# MUX.net
KiCad netlist of a schematic drawn in Altium Designer
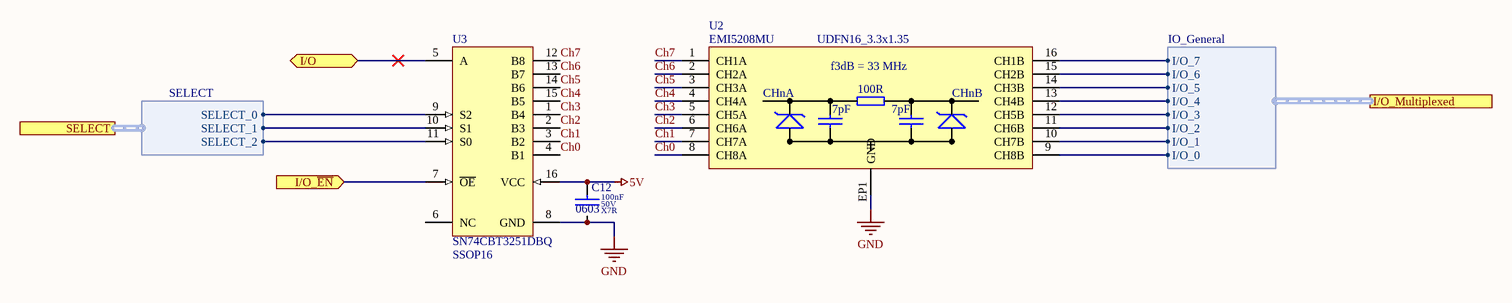
[diagram p0: MUX.SchDoc]

(export (version "E")
  (design (tool "Eeschema 10.0.6"))
  (components
    (comp (ref "C12")
      (value "100nF")
      (footprint "C_0603_1608")
      (description "Capacitor")
      (fields
        (field (name "DIELECTRIC") "X7R")
        (field (name "VOLTAGE") "50V")
        (field (name "SCH_FOOTPRINT") "0603")
        (field (name "PART NUMBER") "C_100nF_50V_X7R_0603_5")
        (field (name "MANUFACTURER") "Samsung")
      )
      (libsource (lib "Library") (part "C"))
    )
    (comp (ref "U2")
      (value "EMI5208MU")
      (footprint "UDFN16_3.3x1.35")
      (description "8 - channel esd-protection + lo-pass filter")
      (fields
        (field (name "SCH_FOOTPRINT") "UDFN16_3.3x1.35")
        (field (name "PART NUMBER") "U_EMI5208MU")
        (field (name "MANUFACTURER") "ON Semiconductor")
      )
      (libsource (lib "Library") (part "U_EMI5208MU"))
    )
    (comp (ref "U3")
      (value "SN74CBT3251DBQ")
      (footprint "SSOP16_4.9x3.9")
      (fields
        (field (name "PART NUMBER") "U_SN74CBT3251DBQ")
        (field (name "SCH_FOOTPRINT") "SSOP16")
        (field (name "MANUFACTURER") "Texas Instruments")
        (field (name "Comment") "1-of-8 FET Multiplexer and Demultiplexer")
      )
      (libsource (lib "Library") (part "U_SN74CBT3251"))
    )
  )
  (nets
    (net (code "3") (name "/Ch0") (class "Default")
      (node (ref "U2") (pin "8") (pinfunction "CH8A_8") (pintype "passive"))
      (node (ref "U3") (pin "4") (pinfunction "B1_4") (pintype "passive"))
    )
    (net (code "4") (name "/Ch1") (class "Default")
      (node (ref "U2") (pin "7") (pinfunction "CH7A_7") (pintype "passive"))
      (node (ref "U3") (pin "3") (pinfunction "B2_3") (pintype "passive"))
    )
    (net (code "5") (name "/Ch2") (class "Default")
      (node (ref "U2") (pin "6") (pinfunction "CH6A_6") (pintype "passive"))
      (node (ref "U3") (pin "2") (pinfunction "B3_2") (pintype "passive"))
    )
    (net (code "6") (name "/Ch3") (class "Default")
      (node (ref "U2") (pin "5") (pinfunction "CH5A_5") (pintype "passive"))
      (node (ref "U3") (pin "1") (pinfunction "B4_1") (pintype "passive"))
    )
    (net (code "7") (name "/Ch4") (class "Default")
      (node (ref "U2") (pin "4") (pinfunction "CH4A_4") (pintype "passive"))
      (node (ref "U3") (pin "15") (pinfunction "B5_15") (pintype "passive"))
    )
    (net (code "8") (name "/Ch5") (class "Default")
      (node (ref "U2") (pin "3") (pinfunction "CH3A_3") (pintype "passive"))
      (node (ref "U3") (pin "14") (pinfunction "B6_14") (pintype "passive"))
    )
    (net (code "9") (name "/Ch6") (class "Default")
      (node (ref "U2") (pin "2") (pinfunction "CH2A_2") (pintype "passive"))
      (node (ref "U3") (pin "13") (pinfunction "B7_13") (pintype "passive"))
    )
    (net (code "10") (name "/Ch7") (class "Default")
      (node (ref "U2") (pin "1") (pinfunction "CH1A_1") (pintype "passive"))
      (node (ref "U3") (pin "12") (pinfunction "B8_12") (pintype "passive"))
    )
    (net (code "11") (name "/I{slash}O") (class "Default")
      (node (ref "U3") (pin "5") (pinfunction "A_5") (pintype "passive"))
    )
    (net (code "12") (name "/I{slash}O_0") (class "Default")
      (node (ref "U2") (pin "9") (pinfunction "CH8B_9") (pintype "passive"))
    )
    (net (code "13") (name "/I{slash}O_1") (class "Default")
      (node (ref "U2") (pin "10") (pinfunction "CH7B_10") (pintype "passive"))
    )
    (net (code "14") (name "/I{slash}O_2") (class "Default")
      (node (ref "U2") (pin "11") (pinfunction "CH6B_11") (pintype "passive"))
    )
    (net (code "15") (name "/I{slash}O_3") (class "Default")
      (node (ref "U2") (pin "12") (pinfunction "CH5B_12") (pintype "passive"))
    )
    (net (code "16") (name "/I{slash}O_4") (class "Default")
      (node (ref "U2") (pin "13") (pinfunction "CH4B_13") (pintype "passive"))
    )
    (net (code "17") (name "/I{slash}O_5") (class "Default")
      (node (ref "U2") (pin "14") (pinfunction "CH3B_14") (pintype "passive"))
    )
    (net (code "18") (name "/I{slash}O_6") (class "Default")
      (node (ref "U2") (pin "15") (pinfunction "CH2B_15") (pintype "passive"))
    )
    (net (code "19") (name "/I{slash}O_7") (class "Default")
      (node (ref "U2") (pin "16") (pinfunction "CH1B_16") (pintype "passive"))
    )
    (net (code "20") (name "/I{slash}O_~{EN}") (class "Default")
      (node (ref "U3") (pin "7") (pinfunction "~{OE}_7") (pintype "input"))
    )
    (net (code "21") (name "/SELECT_0") (class "Default")
      (node (ref "U3") (pin "9") (pinfunction "S2_9") (pintype "input"))
    )
    (net (code "22") (name "/SELECT_1") (class "Default")
      (node (ref "U3") (pin "10") (pinfunction "S1_10") (pintype "input"))
    )
    (net (code "23") (name "/SELECT_2") (class "Default")
      (node (ref "U3") (pin "11") (pinfunction "S0_11") (pintype "input"))
    )
    (net (code "26") (name "5V") (class "Default")
      (node (ref "C12") (pin "1") (pinfunction "1_1") (pintype "passive"))
      (node (ref "U3") (pin "16") (pinfunction "VCC_16") (pintype "input"))
    )
    (net (code "27") (name "GND") (class "Default")
      (node (ref "C12") (pin "2") (pinfunction "2_2") (pintype "passive"))
      (node (ref "U2") (pin "EP1") (pinfunction "GND_EP1") (pintype "power_in"))
      (node (ref "U3") (pin "8") (pinfunction "GND_8") (pintype "power_in"))
    )
    (net (code "28") (name "unconnected-(U3-NC-Pad6)") (class "Default")
      (node (ref "U3") (pin "6") (pinfunction "NC_6") (pintype "passive"))
    )
  )
)
